# ssm.net
KiCad netlist of a schematic drawn in EAGLE
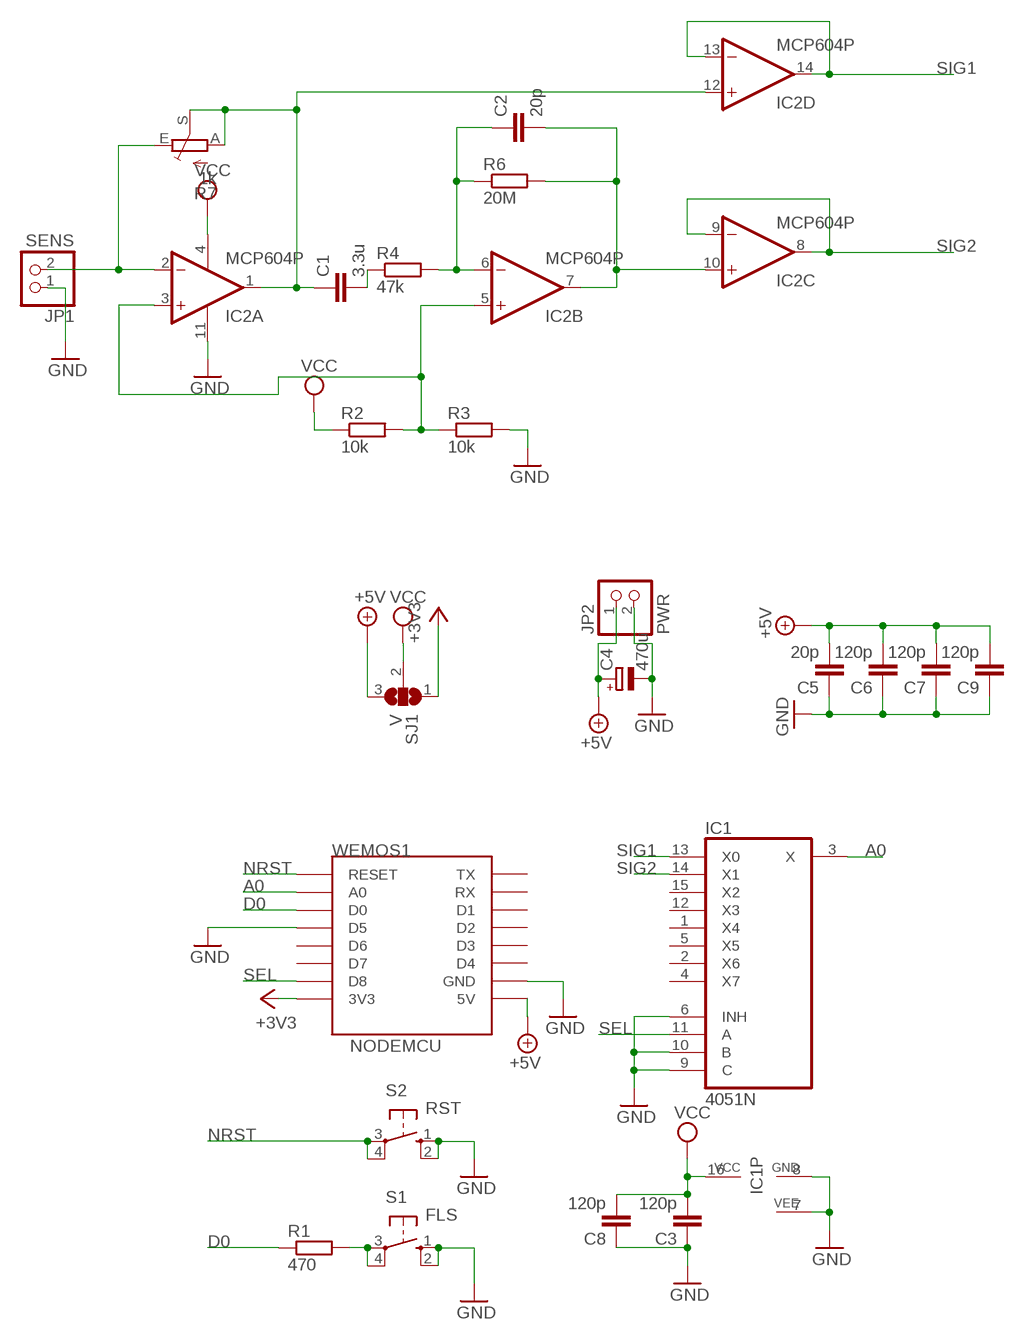
[diagram p0: schematic, sheet 1]

(export (version "E")
  (design (tool "Eeschema 10.0.6"))
  (components
    (comp (ref "C1")
      (value "3.3u")
      (footprint "eagle-import:C225-087X210")
      (libsource (lib "eagle-import") (part "C-EU"))
    )
    (comp (ref "C2")
      (value "20p")
      (footprint "eagle-import:C025-024X044")
      (libsource (lib "eagle-import") (part "C-EU025-024X044"))
    )
    (comp (ref "C3")
      (value "120p")
      (footprint "eagle-import:C025-024X044")
      (libsource (lib "eagle-import") (part "C-EU025-024X044"))
    )
    (comp (ref "C4")
      (value "470u")
      (footprint "eagle-import:E2,5-5")
      (libsource (lib "eagle-import") (part "CPOL-EUE2.5-5"))
    )
    (comp (ref "C5")
      (value "20p")
      (footprint "eagle-import:C025-024X044")
      (libsource (lib "eagle-import") (part "C-EU025-024X044"))
    )
    (comp (ref "C6")
      (value "120p")
      (footprint "eagle-import:C025-024X044")
      (libsource (lib "eagle-import") (part "C-EU025-024X044"))
    )
    (comp (ref "C7")
      (value "120p")
      (footprint "eagle-import:C025-024X044")
      (libsource (lib "eagle-import") (part "C-EU025-024X044"))
    )
    (comp (ref "C8")
      (value "120p")
      (footprint "eagle-import:C025-024X044")
      (libsource (lib "eagle-import") (part "C-EU025-024X044"))
    )
    (comp (ref "C9")
      (value "120p")
      (footprint "eagle-import:C025-024X044")
      (libsource (lib "eagle-import") (part "C-EU025-024X044"))
    )
    (comp (ref "IC1")
      (value "4051N")
      (footprint "eagle-import:DIL16")
      (libsource (lib "eagle-import") (part "4051N"))
    )
    (comp (ref "IC2")
      (value "MCP604P")
      (footprint "eagle-import:DIL14")
      (libsource (lib "eagle-import") (part "MCP604P"))
    )
    (comp (ref "JP1")
      (value "SENS")
      (footprint "eagle-import:1X02")
      (libsource (lib "eagle-import") (part "PINHD-1X2"))
    )
    (comp (ref "JP2")
      (value "PWR")
      (footprint "eagle-import:1X02")
      (libsource (lib "eagle-import") (part "PINHD-1X2"))
    )
    (comp (ref "R1")
      (value "470")
      (footprint "eagle-import:0204_5")
      (libsource (lib "eagle-import") (part "R-EU_0204/5"))
    )
    (comp (ref "R2")
      (value "10k")
      (footprint "eagle-import:0204_7")
      (libsource (lib "eagle-import") (part "resistor_348_R-EU_0204/7"))
    )
    (comp (ref "R3")
      (value "10k")
      (footprint "eagle-import:0204_7")
      (libsource (lib "eagle-import") (part "resistor_348_R-EU_0204/7"))
    )
    (comp (ref "R4")
      (value "47k")
      (footprint "eagle-import:0204_7")
      (libsource (lib "eagle-import") (part "resistor_348_R-EU_0204/7"))
    )
    (comp (ref "R6")
      (value "20M")
      (footprint "eagle-import:0207_10")
      (libsource (lib "eagle-import") (part "R-EU_0207/10"))
    )
    (comp (ref "R7")
      (value "1k")
      (footprint "eagle-import:B64Y")
      (libsource (lib "eagle-import") (part "TRIM_EU-B64Y"))
    )
    (comp (ref "S1")
      (value "FLS")
      (footprint "eagle-import:B3F-10XX")
      (fields (field (name "MPN") "B3F-1000"))
      (libsource (lib "eagle-import") (part "10-XX"))
    )
    (comp (ref "S2")
      (value "RST")
      (footprint "eagle-import:B3F-10XX")
      (fields (field (name "MPN") "B3F-1000"))
      (libsource (lib "eagle-import") (part "10-XX"))
    )
    (comp (ref "SJ1")
      (value "V")
      (footprint "eagle-import:SJ_2")
      (libsource (lib "eagle-import") (part "SJ2W"))
    )
    (comp (ref "WEMOS1")
      (value "NODEMCU")
      (footprint "eagle-import:WEMOS-D1-MINI")
      (libsource (lib "eagle-import") (part "WEMOS-D1-MINI"))
    )
  )
  (nets
    (net (code "1") (name "+3V3") (class "Default")
      (node (ref "SJ1") (pin "1") (pinfunction "1_1") (pintype "passive"))
      (node (ref "WEMOS1") (pin "3V3") (pinfunction "3V3_3V3") (pintype "bidirectional"))
    )
    (net (code "2") (name "+5V") (class "Default")
      (node (ref "C4") (pin "+") (pinfunction "+_+") (pintype "passive"))
      (node (ref "C5") (pin "2") (pinfunction "2_2") (pintype "passive"))
      (node (ref "C6") (pin "2") (pinfunction "2_2") (pintype "passive"))
      (node (ref "C7") (pin "2") (pinfunction "2_2") (pintype "passive"))
      (node (ref "C9") (pin "2") (pinfunction "2_2") (pintype "passive"))
      (node (ref "JP2") (pin "1") (pinfunction "1_1") (pintype "passive"))
      (node (ref "SJ1") (pin "3") (pinfunction "3_3") (pintype "passive"))
      (node (ref "WEMOS1") (pin "5V") (pinfunction "5V_5V") (pintype "bidirectional"))
    )
    (net (code "3") (name "/A0") (class "Default")
      (node (ref "IC1") (pin "3") (pinfunction "X_3") (pintype "bidirectional"))
      (node (ref "WEMOS1") (pin "A0") (pinfunction "A0_A0") (pintype "bidirectional"))
    )
    (net (code "4") (name "/D0") (class "Default")
      (node (ref "R1") (pin "1") (pinfunction "1_1") (pintype "passive"))
      (node (ref "WEMOS1") (pin "D0") (pinfunction "D0_D0") (pintype "bidirectional"))
    )
    (net (code "5") (name "/NRST") (class "Default")
      (node (ref "S2") (pin "3") (pinfunction "P_3") (pintype "passive"))
      (node (ref "S2") (pin "4") (pinfunction "P1_4") (pintype "passive"))
      (node (ref "WEMOS1") (pin "RESET") (pinfunction "RESET_RESET") (pintype "bidirectional"))
    )
    (net (code "6") (name "/SEL") (class "Default")
      (node (ref "IC1") (pin "11") (pinfunction "A_11") (pintype "input"))
      (node (ref "WEMOS1") (pin "D8") (pinfunction "D8_D8") (pintype "bidirectional"))
    )
    (net (code "7") (name "/SIG1") (class "Default")
      (node (ref "IC1") (pin "13") (pinfunction "X0_13") (pintype "bidirectional"))
      (node (ref "IC2") (pin "13") (pinfunction "-IN_13") (pintype "input"))
      (node (ref "IC2") (pin "14") (pinfunction "OUT_14") (pintype "output"))
    )
    (net (code "8") (name "/SIG2") (class "Default")
      (node (ref "IC1") (pin "14") (pinfunction "X1_14") (pintype "bidirectional"))
      (node (ref "IC2") (pin "8") (pinfunction "OUT_8") (pintype "output"))
      (node (ref "IC2") (pin "9") (pinfunction "-IN_9") (pintype "input"))
    )
    (net (code "9") (name "GND") (class "Default")
      (node (ref "C3") (pin "1") (pinfunction "1_1") (pintype "passive"))
      (node (ref "C4") (pin "-") (pinfunction "-_-") (pintype "passive"))
      (node (ref "C5") (pin "1") (pinfunction "1_1") (pintype "passive"))
      (node (ref "C6") (pin "1") (pinfunction "1_1") (pintype "passive"))
      (node (ref "C7") (pin "1") (pinfunction "1_1") (pintype "passive"))
      (node (ref "C8") (pin "1") (pinfunction "1_1") (pintype "passive"))
      (node (ref "C9") (pin "1") (pinfunction "1_1") (pintype "passive"))
      (node (ref "IC1") (pin "10") (pinfunction "B_10") (pintype "input"))
      (node (ref "IC1") (pin "6") (pinfunction "INH_6") (pintype "input"))
      (node (ref "IC1") (pin "7") (pinfunction "VEE_7") (pintype "power_in"))
      (node (ref "IC1") (pin "8") (pinfunction "GND_8") (pintype "power_in"))
      (node (ref "IC1") (pin "9") (pinfunction "C_9") (pintype "input"))
      (node (ref "IC2") (pin "11") (pinfunction "V-_11") (pintype "power_in"))
      (node (ref "JP1") (pin "1") (pinfunction "1_1") (pintype "passive"))
      (node (ref "JP2") (pin "2") (pinfunction "2_2") (pintype "passive"))
      (node (ref "R3") (pin "2") (pinfunction "2_2") (pintype "passive"))
      (node (ref "S1") (pin "1") (pinfunction "S_1") (pintype "passive"))
      (node (ref "S1") (pin "2") (pinfunction "S1_2") (pintype "passive"))
      (node (ref "S2") (pin "1") (pinfunction "S_1") (pintype "passive"))
      (node (ref "S2") (pin "2") (pinfunction "S1_2") (pintype "passive"))
      (node (ref "WEMOS1") (pin "D5") (pinfunction "D5_D5") (pintype "bidirectional"))
      (node (ref "WEMOS1") (pin "GND") (pinfunction "GND_GND") (pintype "bidirectional"))
    )
    (net (code "10") (name "Net-(C1-Pad2)") (class "Default")
      (node (ref "C1") (pin "2") (pinfunction "2_2") (pintype "passive"))
      (node (ref "R4") (pin "1") (pinfunction "1_1") (pintype "passive"))
    )
    (net (code "11") (name "Net-(IC2A-+IN)") (class "Default")
      (node (ref "IC2") (pin "3") (pinfunction "+IN_3") (pintype "input"))
      (node (ref "IC2") (pin "5") (pinfunction "+IN_5") (pintype "input"))
      (node (ref "R2") (pin "2") (pinfunction "2_2") (pintype "passive"))
      (node (ref "R3") (pin "1") (pinfunction "1_1") (pintype "passive"))
    )
    (net (code "12") (name "Net-(IC2A--IN)") (class "Default")
      (node (ref "IC2") (pin "2") (pinfunction "-IN_2") (pintype "input"))
      (node (ref "JP1") (pin "2") (pinfunction "2_2") (pintype "passive"))
      (node (ref "R7") (pin "E") (pinfunction "E_E") (pintype "passive"))
    )
    (net (code "13") (name "Net-(IC2A-OUT)") (class "Default")
      (node (ref "C1") (pin "1") (pinfunction "1_1") (pintype "passive"))
      (node (ref "IC2") (pin "1") (pinfunction "OUT_1") (pintype "output"))
      (node (ref "IC2") (pin "12") (pinfunction "+IN_12") (pintype "input"))
      (node (ref "R7") (pin "A") (pinfunction "A_A") (pintype "passive"))
      (node (ref "R7") (pin "S") (pinfunction "S_S") (pintype "passive"))
    )
    (net (code "14") (name "Net-(IC2B--IN)") (class "Default")
      (node (ref "C2") (pin "1") (pinfunction "1_1") (pintype "passive"))
      (node (ref "IC2") (pin "6") (pinfunction "-IN_6") (pintype "input"))
      (node (ref "R4") (pin "2") (pinfunction "2_2") (pintype "passive"))
      (node (ref "R6") (pin "1") (pinfunction "1_1") (pintype "passive"))
    )
    (net (code "15") (name "Net-(IC2B-OUT)") (class "Default")
      (node (ref "C2") (pin "2") (pinfunction "2_2") (pintype "passive"))
      (node (ref "IC2") (pin "10") (pinfunction "+IN_10") (pintype "input"))
      (node (ref "IC2") (pin "7") (pinfunction "OUT_7") (pintype "output"))
      (node (ref "R6") (pin "2") (pinfunction "2_2") (pintype "passive"))
    )
    (net (code "16") (name "Net-(S1-P)") (class "Default")
      (node (ref "R1") (pin "2") (pinfunction "2_2") (pintype "passive"))
      (node (ref "S1") (pin "3") (pinfunction "P_3") (pintype "passive"))
      (node (ref "S1") (pin "4") (pinfunction "P1_4") (pintype "passive"))
    )
    (net (code "17") (name "VCC") (class "Default")
      (node (ref "C3") (pin "2") (pinfunction "2_2") (pintype "passive"))
      (node (ref "C8") (pin "2") (pinfunction "2_2") (pintype "passive"))
      (node (ref "IC1") (pin "16") (pinfunction "VCC_16") (pintype "power_in"))
      (node (ref "IC2") (pin "4") (pinfunction "V+_4") (pintype "power_in"))
      (node (ref "R2") (pin "1") (pinfunction "1_1") (pintype "passive"))
      (node (ref "SJ1") (pin "2") (pinfunction "2_2") (pintype "passive"))
    )
    (net (code "18") (name "unconnected-(IC1A-X2-Pad15)") (class "Default")
      (node (ref "IC1") (pin "15") (pinfunction "X2_15") (pintype "bidirectional"))
    )
    (net (code "19") (name "unconnected-(IC1A-X3-Pad12)") (class "Default")
      (node (ref "IC1") (pin "12") (pinfunction "X3_12") (pintype "bidirectional"))
    )
    (net (code "20") (name "unconnected-(IC1A-X4-Pad1)") (class "Default")
      (node (ref "IC1") (pin "1") (pinfunction "X4_1") (pintype "bidirectional"))
    )
    (net (code "21") (name "unconnected-(IC1A-X5-Pad5)") (class "Default")
      (node (ref "IC1") (pin "5") (pinfunction "X5_5") (pintype "bidirectional"))
    )
    (net (code "22") (name "unconnected-(IC1A-X6-Pad2)") (class "Default")
      (node (ref "IC1") (pin "2") (pinfunction "X6_2") (pintype "bidirectional"))
    )
    (net (code "23") (name "unconnected-(IC1A-X7-Pad4)") (class "Default")
      (node (ref "IC1") (pin "4") (pinfunction "X7_4") (pintype "bidirectional"))
    )
    (net (code "24") (name "unconnected-(WEMOS1-PadD1)") (class "Default")
      (node (ref "WEMOS1") (pin "D1") (pinfunction "D1_D1") (pintype "bidirectional"))
    )
    (net (code "25") (name "unconnected-(WEMOS1-PadD2)") (class "Default")
      (node (ref "WEMOS1") (pin "D2") (pinfunction "D2_D2") (pintype "bidirectional"))
    )
    (net (code "26") (name "unconnected-(WEMOS1-PadD3)") (class "Default")
      (node (ref "WEMOS1") (pin "D3") (pinfunction "D3_D3") (pintype "bidirectional"))
    )
    (net (code "27") (name "unconnected-(WEMOS1-PadD4)") (class "Default")
      (node (ref "WEMOS1") (pin "D4") (pinfunction "D4_D4") (pintype "bidirectional"))
    )
    (net (code "28") (name "unconnected-(WEMOS1-PadD6)") (class "Default")
      (node (ref "WEMOS1") (pin "D6") (pinfunction "D6_D6") (pintype "bidirectional"))
    )
    (net (code "29") (name "unconnected-(WEMOS1-PadD7)") (class "Default")
      (node (ref "WEMOS1") (pin "D7") (pinfunction "D7_D7") (pintype "bidirectional"))
    )
    (net (code "30") (name "unconnected-(WEMOS1-PadRX)") (class "Default")
      (node (ref "WEMOS1") (pin "RX") (pinfunction "RX_RX") (pintype "bidirectional"))
    )
    (net (code "31") (name "unconnected-(WEMOS1-PadTX)") (class "Default")
      (node (ref "WEMOS1") (pin "TX") (pinfunction "TX_TX") (pintype "bidirectional"))
    )
  )
)
